# Thermal_MGM.net
KiCad netlist of a schematic drawn in Altium Designer
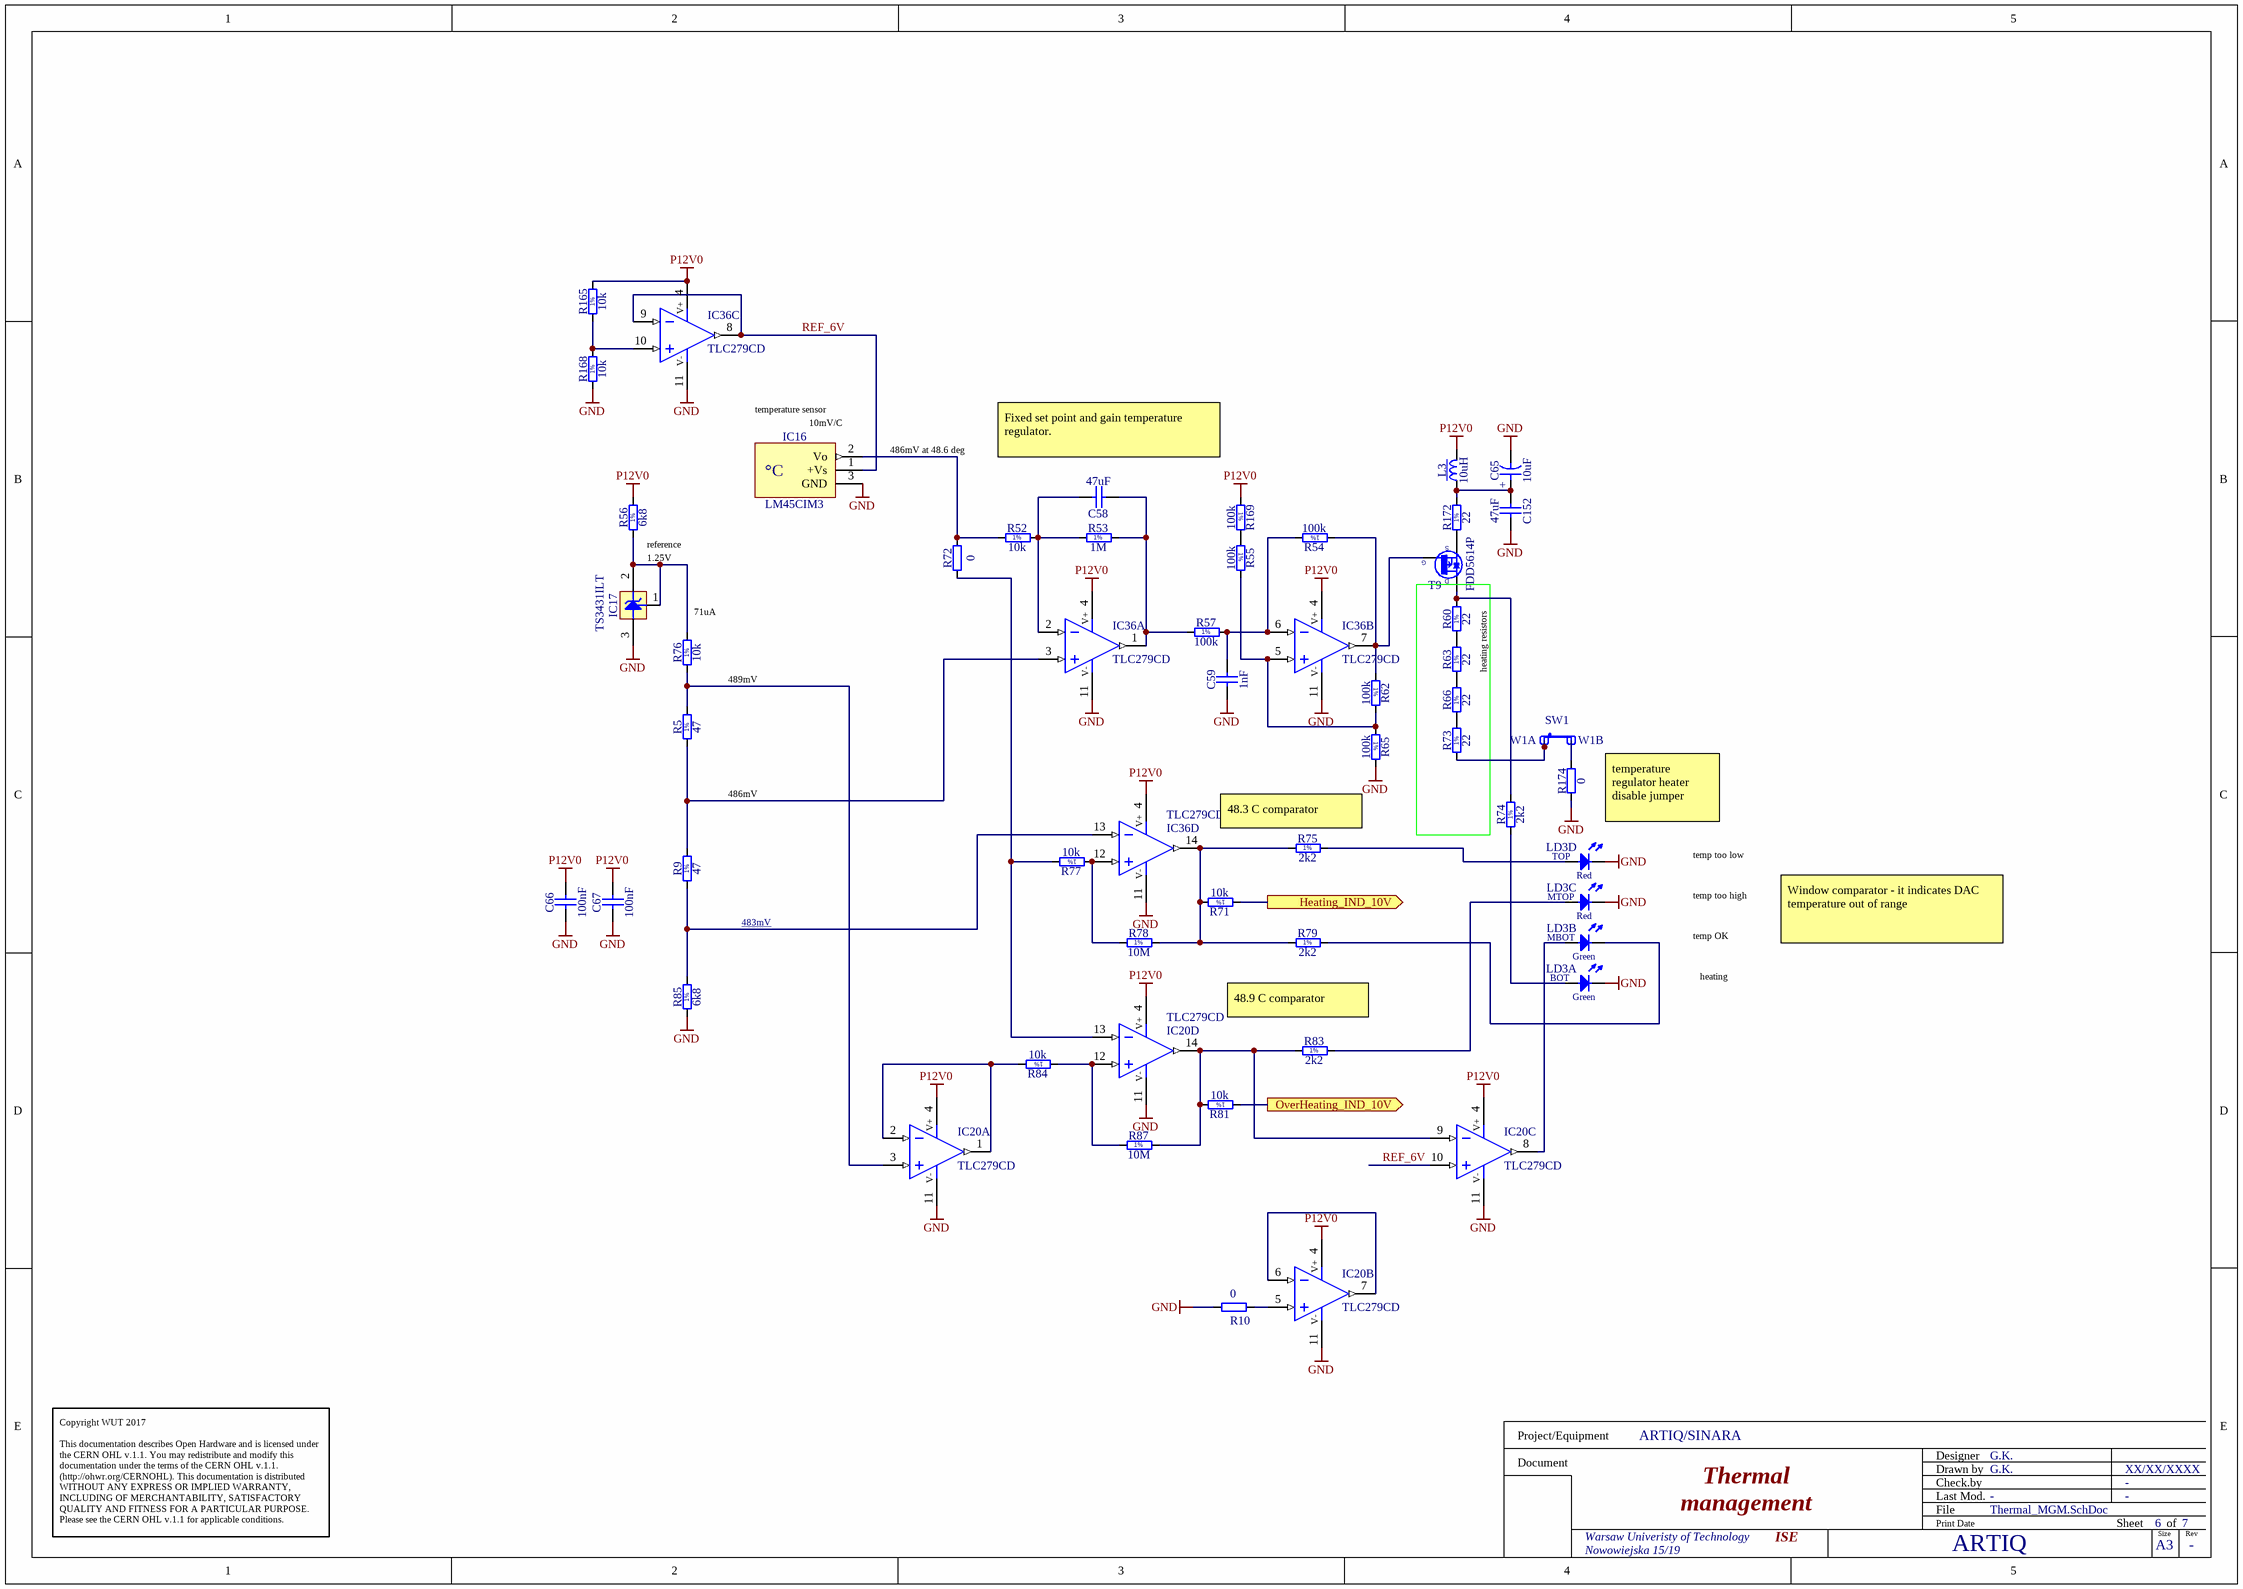
[diagram p0: Thermal_MGM.SchDoc]

(export (version "E")
  (design (tool "Eeschema 10.0.6"))
  (components
    (comp (ref "C58")
      (value "47uF")
      (footprint "CAPC3225X270N")
      (description "Non-polarised capacitor")
      (fields
        (field (name "PART NUMBER") "CC1210_47UF_10V_10%_X7R")
        (field (name "VOLTAGE") "10V")
        (field (name "AUTHOR") "CERN DEM BC")
      )
      (libsource (lib "Capacitors") (part "Capacitor - non polarized"))
    )
    (comp (ref "C59")
      (value "1nF")
      (footprint "CAPC1608X87N")
      (description "Non-polarised capacitor")
      (fields
        (field (name "PART NUMBER") "CC0603_1NF_50V_10%_X7R")
        (field (name "VOLTAGE") "50V")
        (field (name "AUTHOR") "CERN DEM JLC")
      )
      (libsource (lib "Capacitors") (part "Capacitor - non polarized"))
    )
    (comp (ref "C65")
      (value "10uF")
      (footprint "CAPMP3216X180N")
      (description "Polarised capacitor")
      (fields
        (field (name "PART NUMBER") "CTE3216-18_10UF_16V_20%_AVX_TCJ")
        (field (name "VOLTAGE") "16V")
        (field (name "AUTHOR") "CERN DEM JLC")
      )
      (libsource (lib "Capacitors") (part "Capacitor - polarized"))
    )
    (comp (ref "C66")
      (value "100nF")
      (footprint "CAPC1005X55N")
      (description "Non-polarised capacitor")
      (fields
        (field (name "PART NUMBER") "CC0402_100NF_16V_10%_X7R")
        (field (name "VOLTAGE") "16V")
        (field (name "AUTHOR") "CERN DEM JLC")
      )
      (libsource (lib "Capacitors") (part "Capacitor - non polarized"))
    )
    (comp (ref "C67")
      (value "100nF")
      (footprint "CAPC1005X55N")
      (description "Non-polarised capacitor")
      (fields
        (field (name "PART NUMBER") "CC0402_100NF_16V_10%_X7R")
        (field (name "VOLTAGE") "16V")
        (field (name "AUTHOR") "CERN DEM JLC")
      )
      (libsource (lib "Capacitors") (part "Capacitor - non polarized"))
    )
    (comp (ref "C152")
      (value "47uF")
      (footprint "CAPC3225X270N")
      (description "Non-polarised capacitor")
      (fields
        (field (name "PART NUMBER") "CC1210_47UF_10V_10%_X7R")
        (field (name "VOLTAGE") "10V")
        (field (name "AUTHOR") "CERN DEM BC")
      )
      (libsource (lib "Capacitors") (part "Capacitor - non polarized"))
    )
    (comp (ref "IC16")
      (value "LM45CIM3")
      (footprint "SOT95P251X112-3N")
      (description "-20° to +100°C ±3°C Precision Centigrade Temperature Sensors")
      (fields (field (name "MANUFACTURER") "NATIONAL SEMICONDUCTOR") (field (name "AUTHOR") "CERN DEM JLC"))
      (libsource (lib "ICs And Semiconductors") (part "LM45"))
    )
    (comp (ref "IC17")
      (value "TS3431ILT")
      (footprint "SOT95P237X112-3N")
      (description "Precision Reference 1=Adj 2=Cathode 3=Anode")
      (fields (field (name "MANUFACTURER") "ST MICROELECTRONICS") (field (name "AUTHOR") "CERN DEM JLC"))
      (libsource (lib "ICs And Semiconductors") (part "VREF 1ADJ-2C-3A"))
    )
    (comp (ref "IC20")
      (value "TLC279CD")
      (footprint "SOIC127P600X175-14N")
      (description "LinCMOS Precision (900uV) Quad Operational Amplifier")
      (fields (field (name "MANUFACTURER") "TEXAS INSTRUMENTS") (field (name "AUTHOR") "CERN DEM JLC"))
      (libsource (lib "LIBRARY_SCH") (part "OA_TLC279CD"))
    )
    (comp (ref "IC36")
      (value "TLC279CD")
      (footprint "SOIC127P600X175-14N")
      (description "LinCMOS Precision (900uV) Quad Operational Amplifier")
      (fields (field (name "MANUFACTURER") "TEXAS INSTRUMENTS") (field (name "AUTHOR") "CERN DEM JLC"))
      (libsource (lib "LIBRARY_SCH") (part "OA_TLC279CD"))
    )
    (comp (ref "L3")
      (value "10uH")
      (footprint "IND_MURATA-PS_8400")
      (description "Inductor With Core")
      (fields
        (field (name "PART NUMBER") "IND_10UH_10%_MURATA-PS_8400")
        (field (name "POWER") "950mA")
        (field (name "AUTHOR") "CERN DEM JLC")
      )
      (libsource (lib "Inductors & Transformers") (part "Inductor With Magnetic core"))
    )
    (comp (ref "LD3")
      (value "Green/Green/HeRed/HeRed")
      (footprint "LED_BIVAR_H485CHHGGDL")
      (description "LED x4 G-1C2A-BOT_G-3C4A_H-5C6A_H-7C8A-TOP")
      (fields
        (field (name "PART NUMBER") "LED_BIVAR_H485CHHGGDL")
        (field (name "MANUFACTURER") "BIVAR")
        (field (name "AUTHOR") "CERN DEM BC")
      )
      (libsource (lib "ICs And Semiconductors") (part "LED x4 G-1C2A-BOT_G-3C4A_H-5C6A_H-7C8A-TOP"))
    )
    (comp (ref "R5")
      (value "47")
      (footprint "RESC1608X55N")
      (description "Resistor - 1%")
      (fields
        (field (name "PART NUMBER") "R0603_47R_1%_0.1W_100PPM")
        (field (name "POWER") "0.1W")
        (field (name "AUTHOR") "CERN DEM JLC")
      )
      (libsource (lib "Resistors") (part "Resistor - 1%"))
    )
    (comp (ref "R9")
      (value "47")
      (footprint "RESC1608X55N")
      (description "Resistor - 1%")
      (fields
        (field (name "PART NUMBER") "R0603_47R_1%_0.1W_100PPM")
        (field (name "POWER") "0.1W")
        (field (name "AUTHOR") "CERN DEM JLC")
      )
      (libsource (lib "Resistors") (part "Resistor - 1%"))
    )
    (comp (ref "R10")
      (value "0")
      (footprint "RESC1005X40N")
      (description "Resistor")
      (fields
        (field (name "PART NUMBER") "R0402_0R_JUMPER")
        (field (name "MANUFACTURER") "GENERIC")
        (field (name "AUTHOR") "CERN DEM JLC")
      )
      (libsource (lib "Resistors") (part "Resistor"))
    )
    (comp (ref "R52")
      (value "10k")
      (footprint "RESC1608X55N")
      (description "Resistor - 1%")
      (fields
        (field (name "PART NUMBER") "R0603_10K_1%_0.1W_100PPM")
        (field (name "POWER") "0.1W")
        (field (name "AUTHOR") "CERN DEM JLC")
      )
      (libsource (lib "Resistors") (part "Resistor - 1%"))
    )
    (comp (ref "R53")
      (value "1M")
      (footprint "RESC1608X55N")
      (description "Resistor - 1%")
      (fields
        (field (name "PART NUMBER") "R0603_1M_1%_0.1W_100PPM")
        (field (name "POWER") "0.1W")
        (field (name "AUTHOR") "CERN DEM JLC")
      )
      (libsource (lib "Resistors") (part "Resistor - 1%"))
    )
    (comp (ref "R54")
      (value "100k")
      (footprint "RESC1608X55N")
      (description "Resistor - 1%")
      (fields
        (field (name "PART NUMBER") "R0603_100K_1%_0.1W_100PPM")
        (field (name "POWER") "0.1W")
        (field (name "AUTHOR") "CERN DEM JLC")
      )
      (libsource (lib "Resistors") (part "Resistor - 1%"))
    )
    (comp (ref "R55")
      (value "100k")
      (footprint "RESC1608X55N")
      (description "Resistor - 1%")
      (fields
        (field (name "PART NUMBER") "R0603_100K_1%_0.1W_100PPM")
        (field (name "POWER") "0.1W")
        (field (name "AUTHOR") "CERN DEM JLC")
      )
      (libsource (lib "Resistors") (part "Resistor - 1%"))
    )
    (comp (ref "R56")
      (value "6k8")
      (footprint "RESC1608X55N")
      (description "Resistor - 1%")
      (fields
        (field (name "PART NUMBER") "R0603_6K8_1%_0.1W_100PPM")
        (field (name "POWER") "0.1W")
        (field (name "AUTHOR") "CERN DEM JLC")
      )
      (libsource (lib "Resistors") (part "Resistor - 1%"))
    )
    (comp (ref "R57")
      (value "100k")
      (footprint "RESC1608X55N")
      (description "Resistor - 1%")
      (fields
        (field (name "PART NUMBER") "R0603_100K_1%_0.1W_100PPM")
        (field (name "POWER") "0.1W")
        (field (name "AUTHOR") "CERN DEM JLC")
      )
      (libsource (lib "Resistors") (part "Resistor - 1%"))
    )
    (comp (ref "R60")
      (value "22")
      (footprint "RESC3216X65N")
      (description "Resistor - 1%")
      (fields
        (field (name "PART NUMBER") "R1206_22R_1%_0.25W_100PPM")
        (field (name "POWER") "0.25W")
        (field (name "AUTHOR") "CERN DEM JLC")
      )
      (libsource (lib "Resistors") (part "Resistor - 1%"))
    )
    (comp (ref "R62")
      (value "100k")
      (footprint "RESC1608X55N")
      (description "Resistor - 1%")
      (fields
        (field (name "PART NUMBER") "R0603_100K_1%_0.1W_100PPM")
        (field (name "POWER") "0.1W")
        (field (name "AUTHOR") "CERN DEM JLC")
      )
      (libsource (lib "Resistors") (part "Resistor - 1%"))
    )
    (comp (ref "R63")
      (value "22")
      (footprint "RESC3216X65N")
      (description "Resistor - 1%")
      (fields
        (field (name "PART NUMBER") "R1206_22R_1%_0.25W_100PPM")
        (field (name "POWER") "0.25W")
        (field (name "AUTHOR") "CERN DEM JLC")
      )
      (libsource (lib "Resistors") (part "Resistor - 1%"))
    )
    (comp (ref "R65")
      (value "100k")
      (footprint "RESC1608X55N")
      (description "Resistor - 1%")
      (fields
        (field (name "PART NUMBER") "R0603_100K_1%_0.1W_100PPM")
        (field (name "POWER") "0.1W")
        (field (name "AUTHOR") "CERN DEM JLC")
      )
      (libsource (lib "Resistors") (part "Resistor - 1%"))
    )
    (comp (ref "R66")
      (value "22")
      (footprint "RESC3216X65N")
      (description "Resistor - 1%")
      (fields
        (field (name "PART NUMBER") "R1206_22R_1%_0.25W_100PPM")
        (field (name "POWER") "0.25W")
        (field (name "AUTHOR") "CERN DEM JLC")
      )
      (libsource (lib "Resistors") (part "Resistor - 1%"))
    )
    (comp (ref "R71")
      (value "10k")
      (footprint "RESC1608X55N")
      (description "Resistor - 1%")
      (fields
        (field (name "PART NUMBER") "R0603_10K_1%_0.1W_100PPM")
        (field (name "POWER") "0.1W")
        (field (name "AUTHOR") "CERN DEM JLC")
      )
      (libsource (lib "Resistors") (part "Resistor - 1%"))
    )
    (comp (ref "R72")
      (value "0")
      (footprint "RESC1005X40N")
      (description "Resistor")
      (fields
        (field (name "PART NUMBER") "R0402_0R_JUMPER")
        (field (name "MANUFACTURER") "GENERIC")
        (field (name "AUTHOR") "CERN DEM JLC")
      )
      (libsource (lib "Resistors") (part "Resistor"))
    )
    (comp (ref "R73")
      (value "22")
      (footprint "RESC3216X65N")
      (description "Resistor - 1%")
      (fields
        (field (name "PART NUMBER") "R1206_22R_1%_0.25W_100PPM")
        (field (name "POWER") "0.25W")
        (field (name "AUTHOR") "CERN DEM JLC")
      )
      (libsource (lib "Resistors") (part "Resistor - 1%"))
    )
    (comp (ref "R74")
      (value "2k2")
      (footprint "RESC1608X55N")
      (description "Resistor - 1%")
      (fields
        (field (name "PART NUMBER") "R0603_2K2_1%_0.1W_100PPM")
        (field (name "POWER") "0.1W")
        (field (name "AUTHOR") "CERN DEM JLC")
      )
      (libsource (lib "Resistors") (part "Resistor - 1%"))
    )
    (comp (ref "R75")
      (value "2k2")
      (footprint "RESC1608X55N")
      (description "Resistor - 1%")
      (fields
        (field (name "PART NUMBER") "R0603_2K2_1%_0.1W_100PPM")
        (field (name "POWER") "0.1W")
        (field (name "AUTHOR") "CERN DEM JLC")
      )
      (libsource (lib "Resistors") (part "Resistor - 1%"))
    )
    (comp (ref "R76")
      (value "10k")
      (footprint "RESC1608X55N")
      (description "Resistor - 1%")
      (fields
        (field (name "PART NUMBER") "R0603_10K_1%_0.1W_100PPM")
        (field (name "POWER") "0.1W")
        (field (name "AUTHOR") "CERN DEM JLC")
      )
      (libsource (lib "Resistors") (part "Resistor - 1%"))
    )
    (comp (ref "R77")
      (value "10k")
      (footprint "RESC1608X55N")
      (description "Resistor - 1%")
      (fields
        (field (name "PART NUMBER") "R0603_10K_1%_0.1W_100PPM")
        (field (name "POWER") "0.1W")
        (field (name "AUTHOR") "CERN DEM JLC")
      )
      (libsource (lib "Resistors") (part "Resistor - 1%"))
    )
    (comp (ref "R78")
      (value "10M")
      (footprint "RESC1508X63N")
      (description "Resistor - 1%")
      (fields
        (field (name "PART NUMBER") "R0603_10M_1%_0.125W_100PPM_VISHAY_CHP")
        (field (name "POWER") "0.125W")
        (field (name "AUTHOR") "CERN DEM JLC")
      )
      (libsource (lib "Resistors") (part "Resistor - 1%"))
    )
    (comp (ref "R79")
      (value "2k2")
      (footprint "RESC1608X55N")
      (description "Resistor - 1%")
      (fields
        (field (name "PART NUMBER") "R0603_2K2_1%_0.1W_100PPM")
        (field (name "POWER") "0.1W")
        (field (name "AUTHOR") "CERN DEM JLC")
      )
      (libsource (lib "Resistors") (part "Resistor - 1%"))
    )
    (comp (ref "R81")
      (value "10k")
      (footprint "RESC1608X55N")
      (description "Resistor - 1%")
      (fields
        (field (name "PART NUMBER") "R0603_10K_1%_0.1W_100PPM")
        (field (name "POWER") "0.1W")
        (field (name "AUTHOR") "CERN DEM JLC")
      )
      (libsource (lib "Resistors") (part "Resistor - 1%"))
    )
    (comp (ref "R83")
      (value "2k2")
      (footprint "RESC1608X55N")
      (description "Resistor - 1%")
      (fields
        (field (name "PART NUMBER") "R0603_2K2_1%_0.1W_100PPM")
        (field (name "POWER") "0.1W")
        (field (name "AUTHOR") "CERN DEM JLC")
      )
      (libsource (lib "Resistors") (part "Resistor - 1%"))
    )
    (comp (ref "R84")
      (value "10k")
      (footprint "RESC1608X55N")
      (description "Resistor - 1%")
      (fields
        (field (name "PART NUMBER") "R0603_10K_1%_0.1W_100PPM")
        (field (name "POWER") "0.1W")
        (field (name "AUTHOR") "CERN DEM JLC")
      )
      (libsource (lib "Resistors") (part "Resistor - 1%"))
    )
    (comp (ref "R85")
      (value "6k8")
      (footprint "RESC1608X55N")
      (description "Resistor - 1%")
      (fields
        (field (name "PART NUMBER") "R0603_6K8_1%_0.1W_100PPM")
        (field (name "POWER") "0.1W")
        (field (name "AUTHOR") "CERN DEM JLC")
      )
      (libsource (lib "Resistors") (part "Resistor - 1%"))
    )
    (comp (ref "R87")
      (value "10M")
      (footprint "RESC1508X63N")
      (description "Resistor - 1%")
      (fields
        (field (name "PART NUMBER") "R0603_10M_1%_0.125W_100PPM_VISHAY_CHP")
        (field (name "POWER") "0.125W")
        (field (name "AUTHOR") "CERN DEM JLC")
      )
      (libsource (lib "Resistors") (part "Resistor - 1%"))
    )
    (comp (ref "R165")
      (value "10k")
      (footprint "RESC1608X55N")
      (description "Resistor - 1%")
      (fields
        (field (name "PART NUMBER") "R0603_10K_1%_0.1W_100PPM")
        (field (name "POWER") "0.1W")
        (field (name "AUTHOR") "CERN DEM JLC")
      )
      (libsource (lib "Resistors") (part "Resistor - 1%"))
    )
    (comp (ref "R168")
      (value "10k")
      (footprint "RESC1608X55N")
      (description "Resistor - 1%")
      (fields
        (field (name "PART NUMBER") "R0603_10K_1%_0.1W_100PPM")
        (field (name "POWER") "0.1W")
        (field (name "AUTHOR") "CERN DEM JLC")
      )
      (libsource (lib "Resistors") (part "Resistor - 1%"))
    )
    (comp (ref "R169")
      (value "100k")
      (footprint "RESC1608X55N")
      (description "Resistor - 1%")
      (fields
        (field (name "PART NUMBER") "R0603_100K_1%_0.1W_100PPM")
        (field (name "POWER") "0.1W")
        (field (name "AUTHOR") "CERN DEM JLC")
      )
      (libsource (lib "Resistors") (part "Resistor - 1%"))
    )
    (comp (ref "R172")
      (value "22")
      (footprint "RESC3216X65N")
      (description "Resistor - 1%")
      (fields
        (field (name "PART NUMBER") "R1206_22R_1%_0.25W_100PPM")
        (field (name "POWER") "0.25W")
        (field (name "AUTHOR") "CERN DEM JLC")
      )
      (libsource (lib "Resistors") (part "Resistor - 1%"))
    )
    (comp (ref "R174")
      (value "0")
      (footprint "RESC1005X40N")
      (description "Resistor")
      (fields
        (field (name "PART NUMBER") "R0402_0R_JUMPER")
        (field (name "MANUFACTURER") "GENERIC")
        (field (name "AUTHOR") "CERN DEM JLC")
      )
      (libsource (lib "Resistors") (part "Resistor"))
    )
    (comp (ref "SW1")
      (value "Jumper Type1")
      (footprint "JUMPER_BLACK_INSULATED_2.54MM")
      (description "Jumper 1 Pin")
      (fields
        (field (name "PART NUMBER") "COMATEL_313.1730.0.00.40.0")
        (field (name "MANUFACTURER") "KONTEK COMATEL")
        (field (name "AUTHOR") "CERN DEM JLC")
      )
      (libsource (lib "Connectors") (part "Jumper Type1"))
    )
    (comp (ref "T9")
      (value "FDD5614P")
      (footprint "TO228P991X238-3N-R546X521")
      (description "P-CHANNEL MOSFET WITH DIODE")
      (fields (field (name "MANUFACTURER") "FAIRCHILD SEMICONDUCTOR") (field (name "AUTHOR") "CERN DEM JLC"))
      (libsource (lib "ICs And Semiconductors") (part "P-MOSFET-D 1G 2S 3D"))
    )
    (comp (ref "W1")
      (value "Test Point")
      (footprint "COMATEL_385.0358.1.02.400")
      (description "2 Mini Wire-Wrap Contact Strip Header")
      (fields
        (field (name "PART NUMBER") "COMATEL_385.0358.1.02.400")
        (field (name "MANUFACTURER") "KONTEK COMATEL")
        (field (name "AUTHOR") "CERN DEM JLC")
      )
      (libsource (lib "Connectors") (part "Wire-Wrap Contact x2"))
    )
  )
  (nets
    (net (code "1") (name "/Heating_IND_10V") (class "Default")
      (node (ref "R71") (pin "1") (pinfunction "1_1") (pintype "passive"))
    )
    (net (code "2") (name "/OverHeating_IND_10V") (class "Default")
      (node (ref "R81") (pin "1") (pinfunction "1_1") (pintype "passive"))
    )
    (net (code "3") (name "/REF_6V") (class "Default")
      (node (ref "IC16") (pin "1") (pinfunction "+Vs_1") (pintype "power_in"))
      (node (ref "IC20") (pin "10") (pinfunction "IN+_10") (pintype "input"))
      (node (ref "IC36") (pin "8") (pinfunction "OUT_8") (pintype "output"))
      (node (ref "IC36") (pin "9") (pinfunction "IN-_9") (pintype "input"))
    )
    (net (code "4") (name "GND") (class "Default")
      (node (ref "C152") (pin "2") (pinfunction "2_2") (pintype "passive"))
      (node (ref "C59") (pin "1") (pinfunction "1_1") (pintype "passive"))
      (node (ref "C65") (pin "2") (pinfunction "2_2") (pintype "passive"))
      (node (ref "C66") (pin "1") (pinfunction "1_1") (pintype "passive"))
      (node (ref "C67") (pin "1") (pinfunction "1_1") (pintype "passive"))
      (node (ref "IC16") (pin "3") (pinfunction "GND_3") (pintype "power_in"))
      (node (ref "IC17") (pin "3") (pinfunction "A_3") (pintype "passive"))
      (node (ref "IC20") (pin "11") (pinfunction "V-_11") (pintype "power_in"))
      (node (ref "IC36") (pin "11") (pinfunction "V-_11") (pintype "power_in"))
      (node (ref "LD3") (pin "1") (pinfunction "C_1") (pintype "passive"))
      (node (ref "LD3") (pin "5") (pinfunction "C_5") (pintype "passive"))
      (node (ref "LD3") (pin "7") (pinfunction "C_7") (pintype "passive"))
      (node (ref "R10") (pin "2") (pinfunction "2_2") (pintype "passive"))
      (node (ref "R168") (pin "1") (pinfunction "1_1") (pintype "passive"))
      (node (ref "R174") (pin "1") (pinfunction "1_1") (pintype "passive"))
      (node (ref "R65") (pin "2") (pinfunction "2_2") (pintype "passive"))
      (node (ref "R85") (pin "1") (pinfunction "1_1") (pintype "passive"))
    )
    (net (code "5") (name "Net-(C152-Pad1)") (class "Default")
      (node (ref "C152") (pin "1") (pinfunction "1_1") (pintype "passive"))
      (node (ref "C65") (pin "1") (pinfunction "1_1") (pintype "passive"))
      (node (ref "L3") (pin "1") (pinfunction "1_1") (pintype "passive"))
      (node (ref "R172") (pin "2") (pinfunction "2_2") (pintype "passive"))
    )
    (net (code "6") (name "Net-(IC16-Vo)") (class "Default")
      (node (ref "IC16") (pin "2") (pinfunction "Vo_2") (pintype "output"))
      (node (ref "R52") (pin "1") (pinfunction "1_1") (pintype "passive"))
      (node (ref "R72") (pin "2") (pinfunction "2_2") (pintype "passive"))
    )
    (net (code "7") (name "Net-(IC17-Adj)") (class "Default")
      (node (ref "IC17") (pin "1") (pinfunction "Adj_1") (pintype "passive"))
      (node (ref "IC17") (pin "2") (pinfunction "C_2") (pintype "passive"))
      (node (ref "R56") (pin "1") (pinfunction "1_1") (pintype "passive"))
      (node (ref "R76") (pin "2") (pinfunction "2_2") (pintype "passive"))
    )
    (net (code "8") (name "Net-(IC20A-IN+)") (class "Default")
      (node (ref "IC20") (pin "3") (pinfunction "IN+_3") (pintype "input"))
      (node (ref "R5") (pin "2") (pinfunction "2_2") (pintype "passive"))
      (node (ref "R76") (pin "1") (pinfunction "1_1") (pintype "passive"))
    )
    (net (code "9") (name "Net-(IC20A-IN-)") (class "Default")
      (node (ref "IC20") (pin "1") (pinfunction "OUT_1") (pintype "output"))
      (node (ref "IC20") (pin "2") (pinfunction "IN-_2") (pintype "input"))
      (node (ref "R84") (pin "2") (pinfunction "2_2") (pintype "passive"))
    )
    (net (code "10") (name "Net-(IC20B-IN+)") (class "Default")
      (node (ref "IC20") (pin "5") (pinfunction "IN+_5") (pintype "input"))
      (node (ref "R10") (pin "1") (pinfunction "1_1") (pintype "passive"))
    )
    (net (code "11") (name "Net-(IC20B-IN-)") (class "Default")
      (node (ref "IC20") (pin "6") (pinfunction "IN-_6") (pintype "input"))
      (node (ref "IC20") (pin "7") (pinfunction "OUT_7") (pintype "output"))
    )
    (net (code "12") (name "Net-(IC20C-IN-)") (class "Default")
      (node (ref "IC20") (pin "14") (pinfunction "OUT_14") (pintype "output"))
      (node (ref "IC20") (pin "9") (pinfunction "IN-_9") (pintype "input"))
      (node (ref "R81") (pin "2") (pinfunction "2_2") (pintype "passive"))
      (node (ref "R83") (pin "1") (pinfunction "1_1") (pintype "passive"))
      (node (ref "R87") (pin "2") (pinfunction "2_2") (pintype "passive"))
    )
    (net (code "13") (name "Net-(IC20C-OUT)") (class "Default")
      (node (ref "IC20") (pin "8") (pinfunction "OUT_8") (pintype "output"))
      (node (ref "LD3") (pin "4") (pinfunction "A_4") (pintype "passive"))
    )
    (net (code "14") (name "Net-(IC20D-IN+)") (class "Default")
      (node (ref "IC20") (pin "12") (pinfunction "IN+_12") (pintype "input"))
      (node (ref "R84") (pin "1") (pinfunction "1_1") (pintype "passive"))
      (node (ref "R87") (pin "1") (pinfunction "1_1") (pintype "passive"))
    )
    (net (code "15") (name "Net-(IC20D-IN-)") (class "Default")
      (node (ref "IC20") (pin "13") (pinfunction "IN-_13") (pintype "input"))
      (node (ref "R72") (pin "1") (pinfunction "1_1") (pintype "passive"))
      (node (ref "R77") (pin "2") (pinfunction "2_2") (pintype "passive"))
    )
    (net (code "16") (name "Net-(IC36A-IN+)") (class "Default")
      (node (ref "IC36") (pin "3") (pinfunction "IN+_3") (pintype "input"))
      (node (ref "R5") (pin "1") (pinfunction "1_1") (pintype "passive"))
      (node (ref "R9") (pin "2") (pinfunction "2_2") (pintype "passive"))
    )
    (net (code "17") (name "Net-(IC36A-IN-)") (class "Default")
      (node (ref "C58") (pin "2") (pinfunction "2_2") (pintype "passive"))
      (node (ref "IC36") (pin "2") (pinfunction "IN-_2") (pintype "input"))
      (node (ref "R52") (pin "2") (pinfunction "2_2") (pintype "passive"))
      (node (ref "R53") (pin "1") (pinfunction "1_1") (pintype "passive"))
    )
    (net (code "18") (name "Net-(IC36A-OUT)") (class "Default")
      (node (ref "C58") (pin "1") (pinfunction "1_1") (pintype "passive"))
      (node (ref "IC36") (pin "1") (pinfunction "OUT_1") (pintype "output"))
      (node (ref "R53") (pin "2") (pinfunction "2_2") (pintype "passive"))
      (node (ref "R57") (pin "1") (pinfunction "1_1") (pintype "passive"))
    )
    (net (code "19") (name "Net-(IC36B-IN+)") (class "Default")
      (node (ref "IC36") (pin "5") (pinfunction "IN+_5") (pintype "input"))
      (node (ref "R55") (pin "2") (pinfunction "2_2") (pintype "passive"))
      (node (ref "R62") (pin "2") (pinfunction "2_2") (pintype "passive"))
      (node (ref "R65") (pin "1") (pinfunction "1_1") (pintype "passive"))
    )
    (net (code "20") (name "Net-(IC36B-IN-)") (class "Default")
      (node (ref "C59") (pin "2") (pinfunction "2_2") (pintype "passive"))
      (node (ref "IC36") (pin "6") (pinfunction "IN-_6") (pintype "input"))
      (node (ref "R54") (pin "2") (pinfunction "2_2") (pintype "passive"))
      (node (ref "R57") (pin "2") (pinfunction "2_2") (pintype "passive"))
    )
    (net (code "21") (name "Net-(IC36B-OUT)") (class "Default")
      (node (ref "IC36") (pin "7") (pinfunction "OUT_7") (pintype "output"))
      (node (ref "R54") (pin "1") (pinfunction "1_1") (pintype "passive"))
      (node (ref "R62") (pin "1") (pinfunction "1_1") (pintype "passive"))
      (node (ref "T9") (pin "1") (pinfunction "G_1") (pintype "passive"))
    )
    (net (code "22") (name "Net-(IC36C-IN+)") (class "Default")
      (node (ref "IC36") (pin "10") (pinfunction "IN+_10") (pintype "input"))
      (node (ref "R165") (pin "1") (pinfunction "1_1") (pintype "passive"))
      (node (ref "R168") (pin "2") (pinfunction "2_2") (pintype "passive"))
    )
    (net (code "23") (name "Net-(IC36D-IN+)") (class "Default")
      (node (ref "IC36") (pin "12") (pinfunction "IN+_12") (pintype "input"))
      (node (ref "R77") (pin "1") (pinfunction "1_1") (pintype "passive"))
      (node (ref "R78") (pin "1") (pinfunction "1_1") (pintype "passive"))
    )
    (net (code "24") (name "Net-(IC36D-IN-)") (class "Default")
      (node (ref "IC36") (pin "13") (pinfunction "IN-_13") (pintype "input"))
      (node (ref "R85") (pin "2") (pinfunction "2_2") (pintype "passive"))
      (node (ref "R9") (pin "1") (pinfunction "1_1") (pintype "passive"))
    )
    (net (code "25") (name "Net-(IC36D-OUT)") (class "Default")
      (node (ref "IC36") (pin "14") (pinfunction "OUT_14") (pintype "output"))
      (node (ref "R71") (pin "2") (pinfunction "2_2") (pintype "passive"))
      (node (ref "R75") (pin "1") (pinfunction "1_1") (pintype "passive"))
      (node (ref "R78") (pin "2") (pinfunction "2_2") (pintype "passive"))
      (node (ref "R79") (pin "1") (pinfunction "1_1") (pintype "passive"))
    )
    (net (code "26") (name "Net-(LD3A-A)") (class "Default")
      (node (ref "LD3") (pin "2") (pinfunction "A_2") (pintype "passive"))
      (node (ref "R74") (pin "1") (pinfunction "1_1") (pintype "passive"))
    )
    (net (code "27") (name "Net-(LD3B-C)") (class "Default")
      (node (ref "LD3") (pin "3") (pinfunction "C_3") (pintype "passive"))
      (node (ref "R79") (pin "2") (pinfunction "2_2") (pintype "passive"))
    )
    (net (code "28") (name "Net-(LD3C-A)") (class "Default")
      (node (ref "LD3") (pin "6") (pinfunction "A_6") (pintype "passive"))
      (node (ref "R83") (pin "2") (pinfunction "2_2") (pintype "passive"))
    )
    (net (code "29") (name "Net-(LD3D-A)") (class "Default")
      (node (ref "LD3") (pin "8") (pinfunction "A_8") (pintype "passive"))
      (node (ref "R75") (pin "2") (pinfunction "2_2") (pintype "passive"))
    )
    (net (code "30") (name "Net-(R60-Pad1)") (class "Default")
      (node (ref "R60") (pin "1") (pinfunction "1_1") (pintype "passive"))
      (node (ref "R63") (pin "2") (pinfunction "2_2") (pintype "passive"))
    )
    (net (code "31") (name "Net-(R63-Pad1)") (class "Default")
      (node (ref "R63") (pin "1") (pinfunction "1_1") (pintype "passive"))
      (node (ref "R66") (pin "2") (pinfunction "2_2") (pintype "passive"))
    )
    (net (code "32") (name "Net-(R66-Pad1)") (class "Default")
      (node (ref "R66") (pin "1") (pinfunction "1_1") (pintype "passive"))
      (node (ref "R73") (pin "2") (pinfunction "2_2") (pintype "passive"))
    )
    (net (code "33") (name "Net-(R73-Pad1)") (class "Default")
      (node (ref "R73") (pin "1") (pinfunction "1_1") (pintype "passive"))
      (node (ref "SW1") (pin "1") (pinfunction "1_1") (pintype "bidirectional"))
      (node (ref "W1") (pin "1") (pinfunction "1_1") (pintype "bidirectional"))
    )
    (net (code "34") (name "Net-(R169-Pad2)") (class "Default")
      (node (ref "R169") (pin "2") (pinfunction "2_2") (pintype "passive"))
      (node (ref "R55") (pin "1") (pinfunction "1_1") (pintype "passive"))
    )
    (net (code "35") (name "Net-(R174-Pad2)") (class "Default")
      (node (ref "R174") (pin "2") (pinfunction "2_2") (pintype "passive"))
      (node (ref "W1") (pin "2") (pinfunction "2_2") (pintype "bidirectional"))
    )
    (net (code "36") (name "Net-(T9-D)") (class "Default")
      (node (ref "R60") (pin "2") (pinfunction "2_2") (pintype "passive"))
      (node (ref "R74") (pin "2") (pinfunction "2_2") (pintype "passive"))
      (node (ref "T9") (pin "3") (pinfunction "D_3") (pintype "passive"))
    )
    (net (code "37") (name "Net-(T9-S)") (class "Default")
      (node (ref "R172") (pin "1") (pinfunction "1_1") (pintype "passive"))
      (node (ref "T9") (pin "2") (pinfunction "S_2") (pintype "passive"))
    )
    (net (code "38") (name "P12V0") (class "Default")
      (node (ref "C66") (pin "2") (pinfunction "2_2") (pintype "passive"))
      (node (ref "C67") (pin "2") (pinfunction "2_2") (pintype "passive"))
      (node (ref "IC20") (pin "4") (pinfunction "V+_4") (pintype "power_in"))
      (node (ref "IC36") (pin "4") (pinfunction "V+_4") (pintype "power_in"))
      (node (ref "L3") (pin "2") (pinfunction "2_2") (pintype "passive"))
      (node (ref "R165") (pin "2") (pinfunction "2_2") (pintype "passive"))
      (node (ref "R169") (pin "1") (pinfunction "1_1") (pintype "passive"))
      (node (ref "R56") (pin "2") (pinfunction "2_2") (pintype "passive"))
    )
  )
)
